# I2CMux.net
KiCad netlist of a schematic drawn in EAGLE
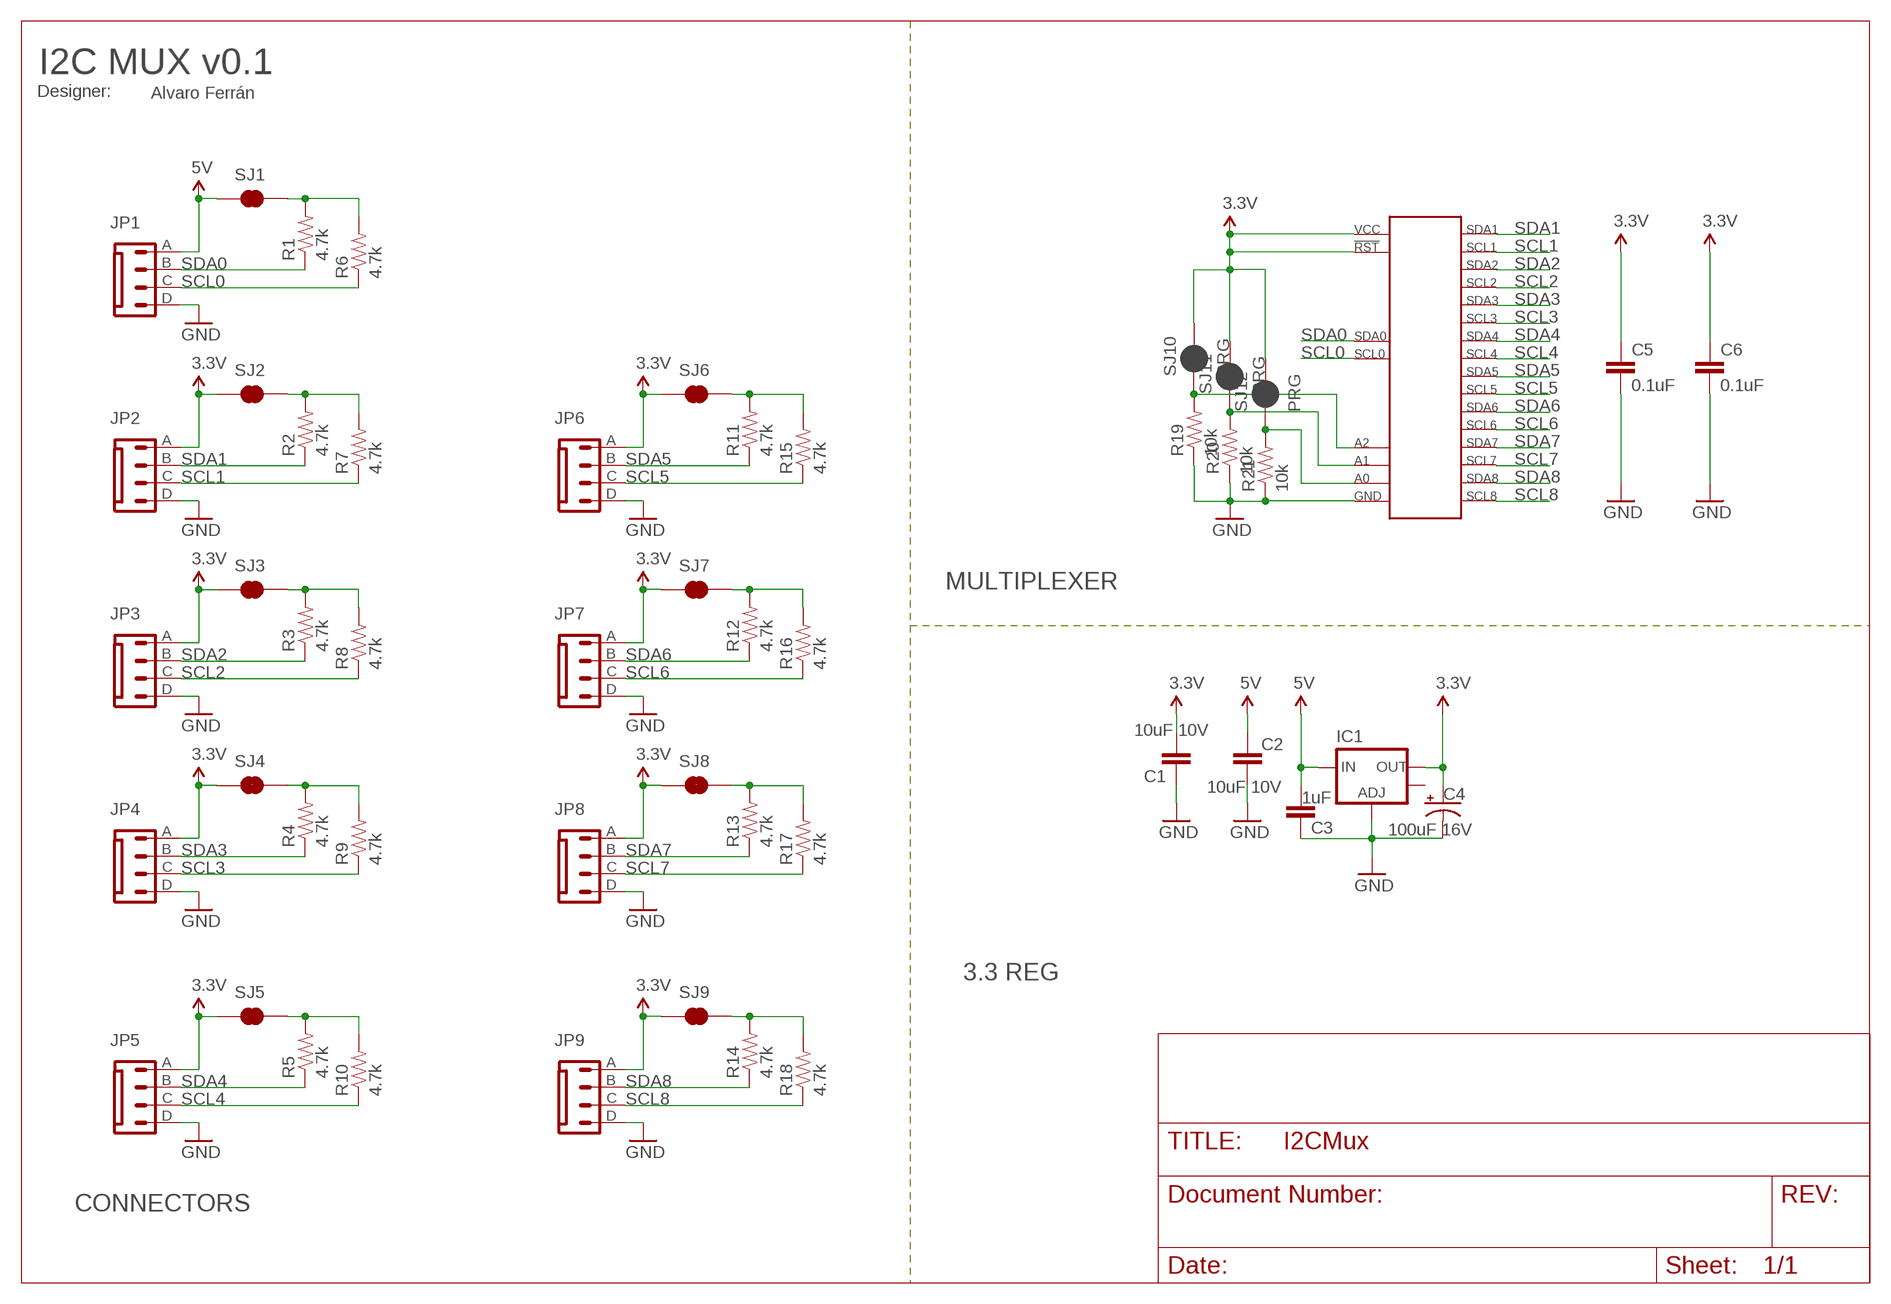
[diagram p0: schematic, sheet 1]

(export (version "E")
  (design (tool "Eeschema 10.0.6"))
  (components
    (comp (ref "C1")
      (value "10uF 10V")
      (footprint "eagle-import:0402-CAP")
      (libsource (lib "eagle-import") (part "CAP0402-CAP"))
    )
    (comp (ref "C2")
      (value "10uF 10V")
      (footprint "eagle-import:0402-CAP")
      (libsource (lib "eagle-import") (part "CAP0402-CAP"))
    )
    (comp (ref "C3")
      (value "1uF")
      (footprint "eagle-import:0402-CAP")
      (libsource (lib "eagle-import") (part "CAP0402-CAP"))
    )
    (comp (ref "C4")
      (value "100uF 16V")
      (footprint "eagle-import:PANASONIC_C")
      (libsource (lib "eagle-import") (part "CAP_POLC"))
    )
    (comp (ref "C5")
      (value "0.1uF")
      (footprint "eagle-import:0402-CAP")
      (libsource (lib "eagle-import") (part "CAP0402-CAP"))
    )
    (comp (ref "C6")
      (value "0.1uF")
      (footprint "eagle-import:0402-CAP")
      (libsource (lib "eagle-import") (part "CAP0402-CAP"))
    )
    (comp (ref "IC1")
      (value "V_REG_LM1117SOT223")
      (footprint "eagle-import:SOT223")
      (libsource (lib "eagle-import") (part "V_REG_LM1117SOT223"))
    )
    (comp (ref "IC2")
      (value "PCA9548A")
      (footprint "eagle-import:PCA9548ABS")
      (libsource (lib "eagle-import") (part "PCA9548A"))
    )
    (comp (ref "JP1")
      (value "MX-6410-04A")
      (footprint "eagle-import:MX-6410-04A")
      (libsource (lib "eagle-import") (part "MX-6410-04A"))
    )
    (comp (ref "JP2")
      (value "MX-6410-04A")
      (footprint "eagle-import:MX-6410-04A")
      (libsource (lib "eagle-import") (part "MX-6410-04A"))
    )
    (comp (ref "JP3")
      (value "MX-6410-04A")
      (footprint "eagle-import:MX-6410-04A")
      (libsource (lib "eagle-import") (part "MX-6410-04A"))
    )
    (comp (ref "JP4")
      (value "MX-6410-04A")
      (footprint "eagle-import:MX-6410-04A")
      (libsource (lib "eagle-import") (part "MX-6410-04A"))
    )
    (comp (ref "JP5")
      (value "MX-6410-04A")
      (footprint "eagle-import:MX-6410-04A")
      (libsource (lib "eagle-import") (part "MX-6410-04A"))
    )
    (comp (ref "JP6")
      (value "MX-6410-04A")
      (footprint "eagle-import:MX-6410-04A")
      (libsource (lib "eagle-import") (part "MX-6410-04A"))
    )
    (comp (ref "JP7")
      (value "MX-6410-04A")
      (footprint "eagle-import:MX-6410-04A")
      (libsource (lib "eagle-import") (part "MX-6410-04A"))
    )
    (comp (ref "JP8")
      (value "MX-6410-04A")
      (footprint "eagle-import:MX-6410-04A")
      (libsource (lib "eagle-import") (part "MX-6410-04A"))
    )
    (comp (ref "JP9")
      (value "MX-6410-04A")
      (footprint "eagle-import:MX-6410-04A")
      (libsource (lib "eagle-import") (part "MX-6410-04A"))
    )
    (comp (ref "R1")
      (value "4.7k")
      (footprint "eagle-import:0402-RES")
      (libsource (lib "eagle-import") (part "RESISTOR0402-RES"))
    )
    (comp (ref "R2")
      (value "4.7k")
      (footprint "eagle-import:0402-RES")
      (libsource (lib "eagle-import") (part "RESISTOR0402-RES"))
    )
    (comp (ref "R3")
      (value "4.7k")
      (footprint "eagle-import:0402-RES")
      (libsource (lib "eagle-import") (part "RESISTOR0402-RES"))
    )
    (comp (ref "R4")
      (value "4.7k")
      (footprint "eagle-import:0402-RES")
      (libsource (lib "eagle-import") (part "RESISTOR0402-RES"))
    )
    (comp (ref "R5")
      (value "4.7k")
      (footprint "eagle-import:0402-RES")
      (libsource (lib "eagle-import") (part "RESISTOR0402-RES"))
    )
    (comp (ref "R6")
      (value "4.7k")
      (footprint "eagle-import:0402-RES")
      (libsource (lib "eagle-import") (part "RESISTOR0402-RES"))
    )
    (comp (ref "R7")
      (value "4.7k")
      (footprint "eagle-import:0402-RES")
      (libsource (lib "eagle-import") (part "RESISTOR0402-RES"))
    )
    (comp (ref "R8")
      (value "4.7k")
      (footprint "eagle-import:0402-RES")
      (libsource (lib "eagle-import") (part "RESISTOR0402-RES"))
    )
    (comp (ref "R9")
      (value "4.7k")
      (footprint "eagle-import:0402-RES")
      (libsource (lib "eagle-import") (part "RESISTOR0402-RES"))
    )
    (comp (ref "R10")
      (value "4.7k")
      (footprint "eagle-import:0402-RES")
      (libsource (lib "eagle-import") (part "RESISTOR0402-RES"))
    )
    (comp (ref "R11")
      (value "4.7k")
      (footprint "eagle-import:0402-RES")
      (libsource (lib "eagle-import") (part "RESISTOR0402-RES"))
    )
    (comp (ref "R12")
      (value "4.7k")
      (footprint "eagle-import:0402-RES")
      (libsource (lib "eagle-import") (part "RESISTOR0402-RES"))
    )
    (comp (ref "R13")
      (value "4.7k")
      (footprint "eagle-import:0402-RES")
      (libsource (lib "eagle-import") (part "RESISTOR0402-RES"))
    )
    (comp (ref "R14")
      (value "4.7k")
      (footprint "eagle-import:0402-RES")
      (libsource (lib "eagle-import") (part "RESISTOR0402-RES"))
    )
    (comp (ref "R15")
      (value "4.7k")
      (footprint "eagle-import:0402-RES")
      (libsource (lib "eagle-import") (part "RESISTOR0402-RES"))
    )
    (comp (ref "R16")
      (value "4.7k")
      (footprint "eagle-import:0402-RES")
      (libsource (lib "eagle-import") (part "RESISTOR0402-RES"))
    )
    (comp (ref "R17")
      (value "4.7k")
      (footprint "eagle-import:0402-RES")
      (libsource (lib "eagle-import") (part "RESISTOR0402-RES"))
    )
    (comp (ref "R18")
      (value "4.7k")
      (footprint "eagle-import:0402-RES")
      (libsource (lib "eagle-import") (part "RESISTOR0402-RES"))
    )
    (comp (ref "R19")
      (value "10k")
      (footprint "eagle-import:0402-RES")
      (libsource (lib "eagle-import") (part "RESISTOR0402-RES"))
    )
    (comp (ref "R20")
      (value "10k")
      (footprint "eagle-import:0402-RES")
      (libsource (lib "eagle-import") (part "RESISTOR0402-RES"))
    )
    (comp (ref "R21")
      (value "10k")
      (footprint "eagle-import:0402-RES")
      (libsource (lib "eagle-import") (part "RESISTOR0402-RES"))
    )
    (comp (ref "SJ1")
      (value "JUMPER-PAD-2-NC_BY_TRACE")
      (footprint "eagle-import:PAD-JUMPER-2-NC_BY_TRACE_YES_SILK")
      (libsource (lib "eagle-import") (part "JUMPER-PAD-2-NC_BY_TRACE"))
    )
    (comp (ref "SJ2")
      (value "JUMPER-PAD-2-NC_BY_TRACE")
      (footprint "eagle-import:PAD-JUMPER-2-NC_BY_TRACE_YES_SILK")
      (libsource (lib "eagle-import") (part "JUMPER-PAD-2-NC_BY_TRACE"))
    )
    (comp (ref "SJ3")
      (value "JUMPER-PAD-2-NC_BY_TRACE")
      (footprint "eagle-import:PAD-JUMPER-2-NC_BY_TRACE_YES_SILK")
      (libsource (lib "eagle-import") (part "JUMPER-PAD-2-NC_BY_TRACE"))
    )
    (comp (ref "SJ4")
      (value "JUMPER-PAD-2-NC_BY_TRACE")
      (footprint "eagle-import:PAD-JUMPER-2-NC_BY_TRACE_YES_SILK")
      (libsource (lib "eagle-import") (part "JUMPER-PAD-2-NC_BY_TRACE"))
    )
    (comp (ref "SJ5")
      (value "JUMPER-PAD-2-NC_BY_TRACE")
      (footprint "eagle-import:PAD-JUMPER-2-NC_BY_TRACE_YES_SILK")
      (libsource (lib "eagle-import") (part "JUMPER-PAD-2-NC_BY_TRACE"))
    )
    (comp (ref "SJ6")
      (value "JUMPER-PAD-2-NC_BY_TRACE")
      (footprint "eagle-import:PAD-JUMPER-2-NC_BY_TRACE_YES_SILK")
      (libsource (lib "eagle-import") (part "JUMPER-PAD-2-NC_BY_TRACE"))
    )
    (comp (ref "SJ7")
      (value "JUMPER-PAD-2-NC_BY_TRACE")
      (footprint "eagle-import:PAD-JUMPER-2-NC_BY_TRACE_YES_SILK")
      (libsource (lib "eagle-import") (part "JUMPER-PAD-2-NC_BY_TRACE"))
    )
    (comp (ref "SJ8")
      (value "JUMPER-PAD-2-NC_BY_TRACE")
      (footprint "eagle-import:PAD-JUMPER-2-NC_BY_TRACE_YES_SILK")
      (libsource (lib "eagle-import") (part "JUMPER-PAD-2-NC_BY_TRACE"))
    )
    (comp (ref "SJ9")
      (value "JUMPER-PAD-2-NC_BY_TRACE")
      (footprint "eagle-import:PAD-JUMPER-2-NC_BY_TRACE_YES_SILK")
      (libsource (lib "eagle-import") (part "JUMPER-PAD-2-NC_BY_TRACE"))
    )
    (comp (ref "SJ10")
      (value "PRG")
      (footprint "eagle-import:PAD-JUMPER-2-NC_BY_PASTE_YES_SILK")
      (libsource (lib "eagle-import") (part "JUMPER-PAD-2-NC_BY_PASTE"))
    )
    (comp (ref "SJ11")
      (value "PRG")
      (footprint "eagle-import:PAD-JUMPER-2-NC_BY_PASTE_YES_SILK")
      (libsource (lib "eagle-import") (part "JUMPER-PAD-2-NC_BY_PASTE"))
    )
    (comp (ref "SJ12")
      (value "PRG")
      (footprint "eagle-import:PAD-JUMPER-2-NC_BY_PASTE_YES_SILK")
      (libsource (lib "eagle-import") (part "JUMPER-PAD-2-NC_BY_PASTE"))
    )
  )
  (nets
    (net (code "1") (name "/SCL0") (class "Default")
      (node (ref "IC2") (pin "19") (pinfunction "SCL0_19") (pintype "bidirectional"))
      (node (ref "JP1") (pin "C") (pinfunction "C_C") (pintype "passive"))
      (node (ref "R6") (pin "1") (pinfunction "1_1") (pintype "passive"))
    )
    (net (code "2") (name "/SCL1") (class "Default")
      (node (ref "IC2") (pin "2") (pinfunction "SCL1_2") (pintype "bidirectional"))
      (node (ref "JP2") (pin "C") (pinfunction "C_C") (pintype "passive"))
      (node (ref "R7") (pin "1") (pinfunction "1_1") (pintype "passive"))
    )
    (net (code "3") (name "/SCL2") (class "Default")
      (node (ref "IC2") (pin "4") (pinfunction "SCL2_4") (pintype "bidirectional"))
      (node (ref "JP3") (pin "C") (pinfunction "C_C") (pintype "passive"))
      (node (ref "R8") (pin "1") (pinfunction "1_1") (pintype "passive"))
    )
    (net (code "4") (name "/SCL3") (class "Default")
      (node (ref "IC2") (pin "6") (pinfunction "SCL3_6") (pintype "bidirectional"))
      (node (ref "JP4") (pin "C") (pinfunction "C_C") (pintype "passive"))
      (node (ref "R9") (pin "1") (pinfunction "1_1") (pintype "passive"))
    )
    (net (code "5") (name "/SCL4") (class "Default")
      (node (ref "IC2") (pin "8") (pinfunction "SCL4_8") (pintype "bidirectional"))
      (node (ref "JP5") (pin "C") (pinfunction "C_C") (pintype "passive"))
      (node (ref "R10") (pin "1") (pinfunction "1_1") (pintype "passive"))
    )
    (net (code "6") (name "/SCL5") (class "Default")
      (node (ref "IC2") (pin "11") (pinfunction "SCL5_11") (pintype "bidirectional"))
      (node (ref "JP6") (pin "C") (pinfunction "C_C") (pintype "passive"))
      (node (ref "R15") (pin "1") (pinfunction "1_1") (pintype "passive"))
    )
    (net (code "7") (name "/SCL6") (class "Default")
      (node (ref "IC2") (pin "13") (pinfunction "SCL6_13") (pintype "bidirectional"))
      (node (ref "JP7") (pin "C") (pinfunction "C_C") (pintype "passive"))
      (node (ref "R16") (pin "1") (pinfunction "1_1") (pintype "passive"))
    )
    (net (code "8") (name "/SCL7") (class "Default")
      (node (ref "IC2") (pin "15") (pinfunction "SCL7_15") (pintype "bidirectional"))
      (node (ref "JP8") (pin "C") (pinfunction "C_C") (pintype "passive"))
      (node (ref "R17") (pin "1") (pinfunction "1_1") (pintype "passive"))
    )
    (net (code "9") (name "/SCL8") (class "Default")
      (node (ref "IC2") (pin "17") (pinfunction "SCL8_17") (pintype "bidirectional"))
      (node (ref "JP9") (pin "C") (pinfunction "C_C") (pintype "passive"))
      (node (ref "R18") (pin "1") (pinfunction "1_1") (pintype "passive"))
    )
    (net (code "10") (name "/SDA0") (class "Default")
      (node (ref "IC2") (pin "20") (pinfunction "SDA0_20") (pintype "bidirectional"))
      (node (ref "JP1") (pin "B") (pinfunction "B_B") (pintype "passive"))
      (node (ref "R1") (pin "1") (pinfunction "1_1") (pintype "passive"))
    )
    (net (code "11") (name "/SDA1") (class "Default")
      (node (ref "IC2") (pin "1") (pinfunction "SDA1_1") (pintype "bidirectional"))
      (node (ref "JP2") (pin "B") (pinfunction "B_B") (pintype "passive"))
      (node (ref "R2") (pin "1") (pinfunction "1_1") (pintype "passive"))
    )
    (net (code "12") (name "/SDA2") (class "Default")
      (node (ref "IC2") (pin "3") (pinfunction "SDA2_3") (pintype "bidirectional"))
      (node (ref "JP3") (pin "B") (pinfunction "B_B") (pintype "passive"))
      (node (ref "R3") (pin "1") (pinfunction "1_1") (pintype "passive"))
    )
    (net (code "13") (name "/SDA3") (class "Default")
      (node (ref "IC2") (pin "5") (pinfunction "SDA3_5") (pintype "bidirectional"))
      (node (ref "JP4") (pin "B") (pinfunction "B_B") (pintype "passive"))
      (node (ref "R4") (pin "1") (pinfunction "1_1") (pintype "passive"))
    )
    (net (code "14") (name "/SDA4") (class "Default")
      (node (ref "IC2") (pin "7") (pinfunction "SDA4_7") (pintype "bidirectional"))
      (node (ref "JP5") (pin "B") (pinfunction "B_B") (pintype "passive"))
      (node (ref "R5") (pin "1") (pinfunction "1_1") (pintype "passive"))
    )
    (net (code "15") (name "/SDA5") (class "Default")
      (node (ref "IC2") (pin "10") (pinfunction "SDA5_10") (pintype "bidirectional"))
      (node (ref "JP6") (pin "B") (pinfunction "B_B") (pintype "passive"))
      (node (ref "R11") (pin "1") (pinfunction "1_1") (pintype "passive"))
    )
    (net (code "16") (name "/SDA6") (class "Default")
      (node (ref "IC2") (pin "12") (pinfunction "SDA6_12") (pintype "bidirectional"))
      (node (ref "JP7") (pin "B") (pinfunction "B_B") (pintype "passive"))
      (node (ref "R12") (pin "1") (pinfunction "1_1") (pintype "passive"))
    )
    (net (code "17") (name "/SDA7") (class "Default")
      (node (ref "IC2") (pin "14") (pinfunction "SDA7_14") (pintype "bidirectional"))
      (node (ref "JP8") (pin "B") (pinfunction "B_B") (pintype "passive"))
      (node (ref "R13") (pin "1") (pinfunction "1_1") (pintype "passive"))
    )
    (net (code "18") (name "/SDA8") (class "Default")
      (node (ref "IC2") (pin "16") (pinfunction "SDA8_16") (pintype "bidirectional"))
      (node (ref "JP9") (pin "B") (pinfunction "B_B") (pintype "passive"))
      (node (ref "R14") (pin "1") (pinfunction "1_1") (pintype "passive"))
    )
    (net (code "19") (name "3.3V") (class "Default")
      (node (ref "C1") (pin "2") (pinfunction "2_2") (pintype "passive"))
      (node (ref "C4") (pin "+") (pinfunction "+_+") (pintype "passive"))
      (node (ref "C5") (pin "1") (pinfunction "1_1") (pintype "passive"))
      (node (ref "C6") (pin "1") (pinfunction "1_1") (pintype "passive"))
      (node (ref "IC1") (pin "2") (pinfunction "OUT_2") (pintype "output"))
      (node (ref "IC2") (pin "21") (pinfunction "VCC_21") (pintype "input"))
      (node (ref "IC2") (pin "24") (pinfunction "~{RESET}_24") (pintype "bidirectional"))
      (node (ref "JP2") (pin "A") (pinfunction "A_A") (pintype "passive"))
      (node (ref "JP3") (pin "A") (pinfunction "A_A") (pintype "passive"))
      (node (ref "JP4") (pin "A") (pinfunction "A_A") (pintype "passive"))
      (node (ref "JP5") (pin "A") (pinfunction "A_A") (pintype "passive"))
      (node (ref "JP6") (pin "A") (pinfunction "A_A") (pintype "passive"))
      (node (ref "JP7") (pin "A") (pinfunction "A_A") (pintype "passive"))
      (node (ref "JP8") (pin "A") (pinfunction "A_A") (pintype "passive"))
      (node (ref "JP9") (pin "A") (pinfunction "A_A") (pintype "passive"))
      (node (ref "SJ10") (pin "2") (pinfunction "2_2") (pintype "passive"))
      (node (ref "SJ11") (pin "2") (pinfunction "2_2") (pintype "passive"))
      (node (ref "SJ12") (pin "2") (pinfunction "2_2") (pintype "passive"))
      (node (ref "SJ2") (pin "1") (pinfunction "1_1") (pintype "passive"))
      (node (ref "SJ3") (pin "1") (pinfunction "1_1") (pintype "passive"))
      (node (ref "SJ4") (pin "1") (pinfunction "1_1") (pintype "passive"))
      (node (ref "SJ5") (pin "1") (pinfunction "1_1") (pintype "passive"))
      (node (ref "SJ6") (pin "1") (pinfunction "1_1") (pintype "passive"))
      (node (ref "SJ7") (pin "1") (pinfunction "1_1") (pintype "passive"))
      (node (ref "SJ8") (pin "1") (pinfunction "1_1") (pintype "passive"))
      (node (ref "SJ9") (pin "1") (pinfunction "1_1") (pintype "passive"))
    )
    (net (code "20") (name "5V") (class "Default")
      (node (ref "C2") (pin "2") (pinfunction "2_2") (pintype "passive"))
      (node (ref "C3") (pin "2") (pinfunction "2_2") (pintype "passive"))
      (node (ref "IC1") (pin "3") (pinfunction "IN_3") (pintype "input"))
      (node (ref "JP1") (pin "A") (pinfunction "A_A") (pintype "passive"))
      (node (ref "SJ1") (pin "1") (pinfunction "1_1") (pintype "passive"))
    )
    (net (code "21") (name "GND") (class "Default")
      (node (ref "C1") (pin "1") (pinfunction "1_1") (pintype "passive"))
      (node (ref "C2") (pin "1") (pinfunction "1_1") (pintype "passive"))
      (node (ref "C3") (pin "1") (pinfunction "1_1") (pintype "passive"))
      (node (ref "C4") (pin "-") (pinfunction "-_-") (pintype "passive"))
      (node (ref "C5") (pin "2") (pinfunction "2_2") (pintype "passive"))
      (node (ref "C6") (pin "2") (pinfunction "2_2") (pintype "passive"))
      (node (ref "IC1") (pin "1") (pinfunction "ADJ_1") (pintype "input"))
      (node (ref "IC2") (pin "9") (pinfunction "GND_9") (pintype "bidirectional"))
      (node (ref "IC2") (pin "THERMAL") (pinfunction "GND_THERMAL") (pintype "bidirectional"))
      (node (ref "JP1") (pin "D") (pinfunction "D_D") (pintype "passive"))
      (node (ref "JP2") (pin "D") (pinfunction "D_D") (pintype "passive"))
      (node (ref "JP3") (pin "D") (pinfunction "D_D") (pintype "passive"))
      (node (ref "JP4") (pin "D") (pinfunction "D_D") (pintype "passive"))
      (node (ref "JP5") (pin "D") (pinfunction "D_D") (pintype "passive"))
      (node (ref "JP6") (pin "D") (pinfunction "D_D") (pintype "passive"))
      (node (ref "JP7") (pin "D") (pinfunction "D_D") (pintype "passive"))
      (node (ref "JP8") (pin "D") (pinfunction "D_D") (pintype "passive"))
      (node (ref "JP9") (pin "D") (pinfunction "D_D") (pintype "passive"))
      (node (ref "R19") (pin "1") (pinfunction "1_1") (pintype "passive"))
      (node (ref "R20") (pin "1") (pinfunction "1_1") (pintype "passive"))
      (node (ref "R21") (pin "1") (pinfunction "1_1") (pintype "passive"))
    )
    (net (code "22") (name "Net-(IC2-A0)") (class "Default")
      (node (ref "IC2") (pin "22") (pinfunction "A0_22") (pintype "bidirectional"))
      (node (ref "R21") (pin "2") (pinfunction "2_2") (pintype "passive"))
      (node (ref "SJ12") (pin "1") (pinfunction "1_1") (pintype "passive"))
    )
    (net (code "23") (name "Net-(IC2-A1)") (class "Default")
      (node (ref "IC2") (pin "23") (pinfunction "A1_23") (pintype "bidirectional"))
      (node (ref "R20") (pin "2") (pinfunction "2_2") (pintype "passive"))
      (node (ref "SJ11") (pin "1") (pinfunction "1_1") (pintype "passive"))
    )
    (net (code "24") (name "Net-(IC2-A2)") (class "Default")
      (node (ref "IC2") (pin "18") (pinfunction "A2_18") (pintype "bidirectional"))
      (node (ref "R19") (pin "2") (pinfunction "2_2") (pintype "passive"))
      (node (ref "SJ10") (pin "1") (pinfunction "1_1") (pintype "passive"))
    )
    (net (code "25") (name "Net-(R1-Pad2)") (class "Default")
      (node (ref "R1") (pin "2") (pinfunction "2_2") (pintype "passive"))
      (node (ref "R6") (pin "2") (pinfunction "2_2") (pintype "passive"))
      (node (ref "SJ1") (pin "2") (pinfunction "2_2") (pintype "passive"))
    )
    (net (code "26") (name "Net-(R2-Pad2)") (class "Default")
      (node (ref "R2") (pin "2") (pinfunction "2_2") (pintype "passive"))
      (node (ref "R7") (pin "2") (pinfunction "2_2") (pintype "passive"))
      (node (ref "SJ2") (pin "2") (pinfunction "2_2") (pintype "passive"))
    )
    (net (code "27") (name "Net-(R3-Pad2)") (class "Default")
      (node (ref "R3") (pin "2") (pinfunction "2_2") (pintype "passive"))
      (node (ref "R8") (pin "2") (pinfunction "2_2") (pintype "passive"))
      (node (ref "SJ3") (pin "2") (pinfunction "2_2") (pintype "passive"))
    )
    (net (code "28") (name "Net-(R4-Pad2)") (class "Default")
      (node (ref "R4") (pin "2") (pinfunction "2_2") (pintype "passive"))
      (node (ref "R9") (pin "2") (pinfunction "2_2") (pintype "passive"))
      (node (ref "SJ4") (pin "2") (pinfunction "2_2") (pintype "passive"))
    )
    (net (code "29") (name "Net-(R10-Pad2)") (class "Default")
      (node (ref "R10") (pin "2") (pinfunction "2_2") (pintype "passive"))
      (node (ref "R5") (pin "2") (pinfunction "2_2") (pintype "passive"))
      (node (ref "SJ5") (pin "2") (pinfunction "2_2") (pintype "passive"))
    )
    (net (code "30") (name "Net-(R11-Pad2)") (class "Default")
      (node (ref "R11") (pin "2") (pinfunction "2_2") (pintype "passive"))
      (node (ref "R15") (pin "2") (pinfunction "2_2") (pintype "passive"))
      (node (ref "SJ6") (pin "2") (pinfunction "2_2") (pintype "passive"))
    )
    (net (code "31") (name "Net-(R12-Pad2)") (class "Default")
      (node (ref "R12") (pin "2") (pinfunction "2_2") (pintype "passive"))
      (node (ref "R16") (pin "2") (pinfunction "2_2") (pintype "passive"))
      (node (ref "SJ7") (pin "2") (pinfunction "2_2") (pintype "passive"))
    )
    (net (code "32") (name "Net-(R13-Pad2)") (class "Default")
      (node (ref "R13") (pin "2") (pinfunction "2_2") (pintype "passive"))
      (node (ref "R17") (pin "2") (pinfunction "2_2") (pintype "passive"))
      (node (ref "SJ8") (pin "2") (pinfunction "2_2") (pintype "passive"))
    )
    (net (code "33") (name "Net-(R14-Pad2)") (class "Default")
      (node (ref "R14") (pin "2") (pinfunction "2_2") (pintype "passive"))
      (node (ref "R18") (pin "2") (pinfunction "2_2") (pintype "passive"))
      (node (ref "SJ9") (pin "2") (pinfunction "2_2") (pintype "passive"))
    )
    (net (code "34") (name "unconnected-(IC1-OUT-Pad4)") (class "Default")
      (node (ref "IC1") (pin "4") (pinfunction "OUT_4") (pintype "output"))
    )
  )
)
